# bdk2m_comm.net
KiCad netlist of a schematic drawn in Altium Designer
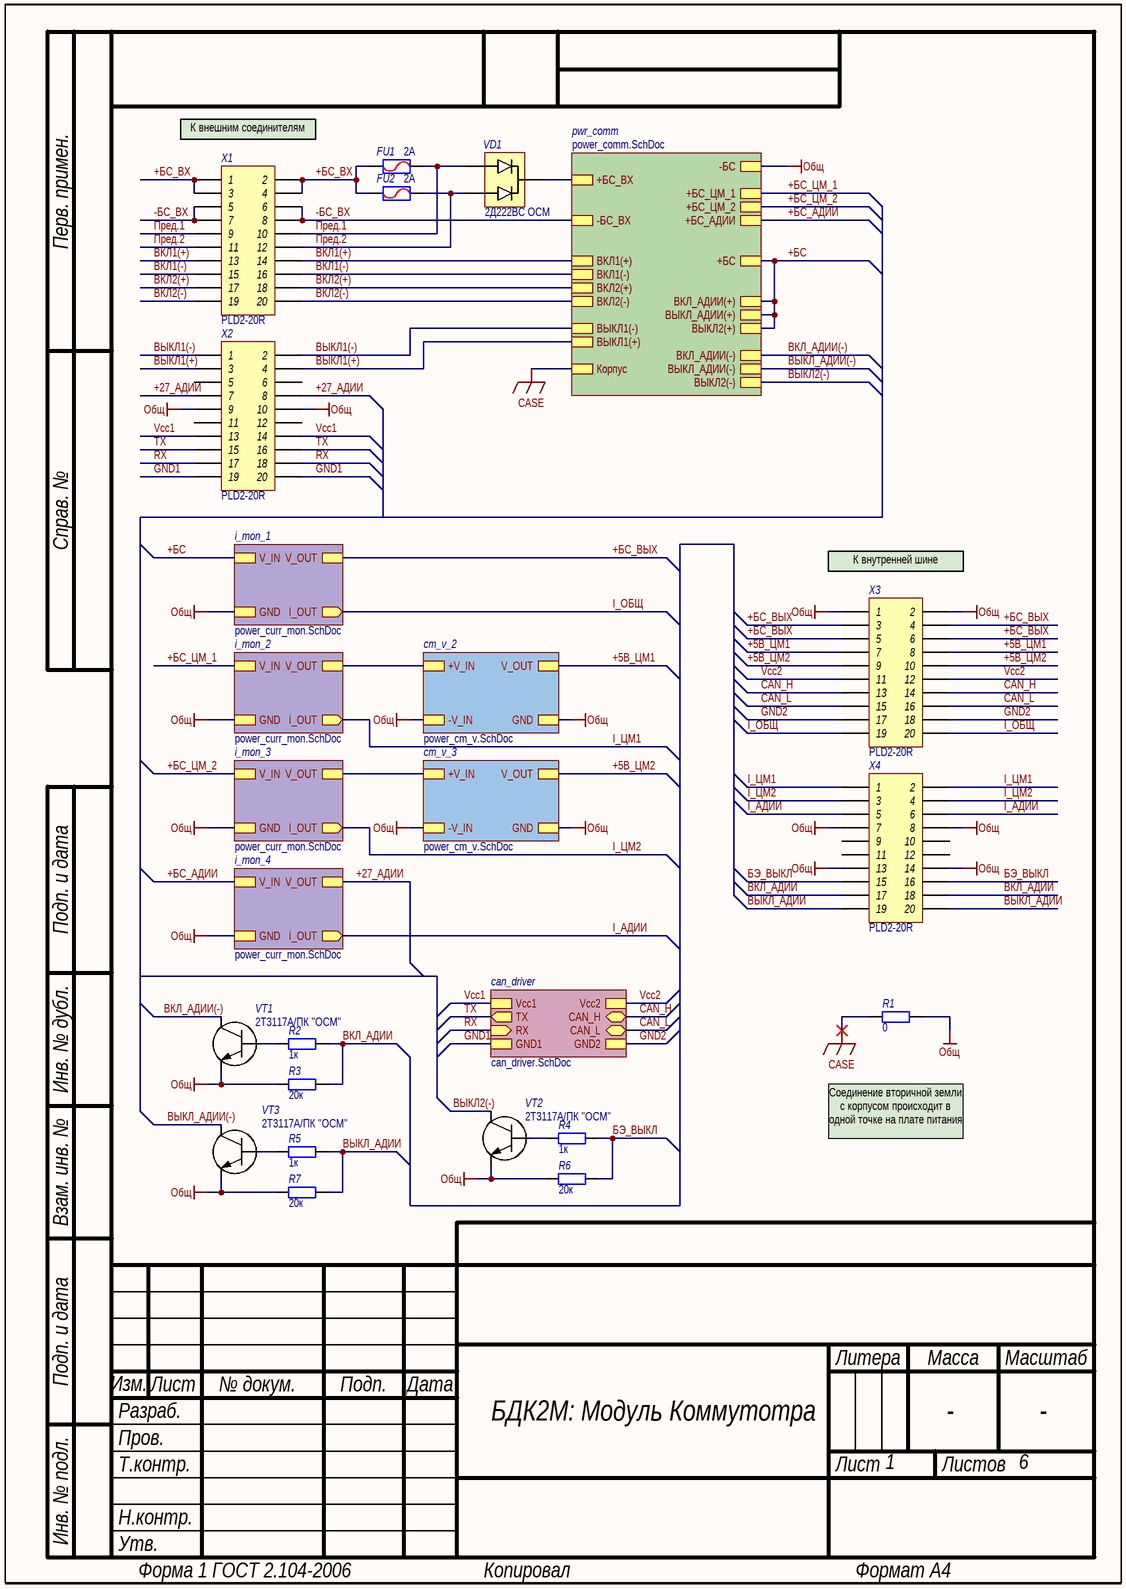
[diagram p0: bdk2m_comm.SchDoc]

(export (version "E")
  (design (tool "Eeschema 10.0.6"))
  (components
    (comp (ref "FU1")
      (value "2A")
      (footprint "VP1-2")
      (description "Предохранитель плавкий")
      (fields (field (name "Comment") "VP1-2"))
      (libsource (lib "VP1-2") (part "VP1-2"))
    )
    (comp (ref "FU2")
      (value "2A")
      (footprint "VP1-2")
      (description "Предохранитель плавкий")
      (fields (field (name "Comment") "VP1-2"))
      (libsource (lib "VP1-2") (part "VP1-2"))
    )
    (comp (ref "R1")
      (value "0")
      (footprint "SMD_0805")
      (description "Resistor")
      (libsource (lib "Passive") (part "Resistor"))
    )
    (comp (ref "R2")
      (value "1к")
      (footprint "SMD_0805")
      (description "Resistor")
      (libsource (lib "Passive") (part "Resistor"))
    )
    (comp (ref "R3")
      (value "20к")
      (footprint "SMD_0805")
      (description "Resistor")
      (libsource (lib "Passive") (part "Resistor"))
    )
    (comp (ref "R4")
      (value "1к")
      (footprint "SMD_0805")
      (description "Resistor")
      (libsource (lib "Passive") (part "Resistor"))
    )
    (comp (ref "R5")
      (value "1к")
      (footprint "SMD_0805")
      (description "Resistor")
      (libsource (lib "Passive") (part "Resistor"))
    )
    (comp (ref "R6")
      (value "20к")
      (footprint "SMD_0805")
      (description "Resistor")
      (libsource (lib "Passive") (part "Resistor"))
    )
    (comp (ref "R7")
      (value "20к")
      (footprint "SMD_0805")
      (description "Resistor")
      (libsource (lib "Passive") (part "Resistor"))
    )
    (comp (ref "VD1")
      (value "2D222VS \"OSM\"")
      (footprint "4116.4-3_offcut")
      (description "Сдвоенный диод")
      (fields (field (name "НАИМЕНОВАНИЕ") "2Д222ВС ОСМ"))
      (libsource (lib "Diod") (part "2D222"))
    )
    (comp (ref "VT1")
      (value "2T3117A")
      (footprint "TO-18")
      (description "Кремниевый биполярный\r\nэпитаксиально-планарный\r\nn-p-n транзистор")
      (fields (field (name "НАИМЕНОВАНИЕ") "2Т3117А/ПК \"ОСМ\""))
      (libsource (lib "Transistor") (part "2T3117A"))
    )
    (comp (ref "VT2")
      (value "2T3117A")
      (footprint "TO-18")
      (description "Кремниевый биполярный\r\nэпитаксиально-планарный\r\nn-p-n транзистор")
      (fields (field (name "НАИМЕНОВАНИЕ") "2Т3117А/ПК \"ОСМ\""))
      (libsource (lib "Transistor") (part "2T3117A"))
    )
    (comp (ref "VT3")
      (value "2T3117A")
      (footprint "TO-18")
      (description "Кремниевый биполярный\r\nэпитаксиально-планарный\r\nn-p-n транзистор")
      (fields (field (name "НАИМЕНОВАНИЕ") "2Т3117А/ПК \"ОСМ\""))
      (libsource (lib "Transistor") (part "2T3117A"))
    )
    (comp (ref "X1")
      (value "Header 2X10")
      (footprint "PLD2-20R")
      (description "Header, 12-Pin, Dual row")
      (fields (field (name "НАИМЕНОВАНИЕ") "PLD2-20R"))
      (libsource (lib "Connector") (part "PLD2-20"))
    )
    (comp (ref "X2")
      (value "Header 2X10")
      (footprint "PLD2-20R")
      (description "Header, 12-Pin, Dual row")
      (fields (field (name "НАИМЕНОВАНИЕ") "PLD2-20R"))
      (libsource (lib "Connector") (part "PLD2-20"))
    )
    (comp (ref "X3")
      (value "Header 2X10")
      (footprint "PLD2-20R")
      (description "Header, 12-Pin, Dual row")
      (fields (field (name "НАИМЕНОВАНИЕ") "PLD2-20R"))
      (libsource (lib "Connector") (part "PLD2-20"))
    )
    (comp (ref "X4")
      (value "Header 2X10")
      (footprint "PLD2-20R")
      (description "Header, 12-Pin, Dual row")
      (fields (field (name "НАИМЕНОВАНИЕ") "PLD2-20R"))
      (libsource (lib "Connector") (part "PLD2-20"))
    )
  )
  (nets
    (net (code "1") (name "/+5В_ЦМ1") (class "Default")
      (node (ref "X3") (pin "7") (pinfunction "7_7") (pintype "passive"))
      (node (ref "X3") (pin "8") (pinfunction "8_8") (pintype "passive"))
    )
    (net (code "2") (name "/+5В_ЦМ2") (class "Default")
      (node (ref "X3") (pin "10") (pinfunction "10_10") (pintype "passive"))
      (node (ref "X3") (pin "9") (pinfunction "9_9") (pintype "passive"))
    )
    (net (code "3") (name "/+27_АДИИ") (class "Default")
      (node (ref "X2") (pin "7") (pinfunction "7_7") (pintype "passive"))
      (node (ref "X2") (pin "8") (pinfunction "8_8") (pintype "passive"))
    )
    (net (code "8") (name "/+БС_ВХ") (class "Default")
      (node (ref "FU1") (pin "1") (pinfunction "1_1") (pintype "passive"))
      (node (ref "FU2") (pin "1") (pinfunction "1_1") (pintype "passive"))
      (node (ref "X1") (pin "1") (pinfunction "1_1") (pintype "passive"))
      (node (ref "X1") (pin "2") (pinfunction "2_2") (pintype "passive"))
      (node (ref "X1") (pin "3") (pinfunction "3_3") (pintype "passive"))
      (node (ref "X1") (pin "4") (pinfunction "4_4") (pintype "passive"))
    )
    (net (code "9") (name "/+БС_ВХ_1") (class "Default") (node (ref "VD1") (pin "8") (pintype "passive")))
    (net (code "10") (name "/+БС_ВЫХ") (class "Default")
      (node (ref "X3") (pin "3") (pinfunction "3_3") (pintype "passive"))
      (node (ref "X3") (pin "4") (pinfunction "4_4") (pintype "passive"))
      (node (ref "X3") (pin "5") (pinfunction "5_5") (pintype "passive"))
      (node (ref "X3") (pin "6") (pinfunction "6_6") (pintype "passive"))
    )
    (net (code "13") (name "/-БС_ВХ") (class "Default")
      (node (ref "X1") (pin "5") (pinfunction "5_5") (pintype "passive"))
      (node (ref "X1") (pin "6") (pinfunction "6_6") (pintype "passive"))
      (node (ref "X1") (pin "7") (pinfunction "7_7") (pintype "passive"))
      (node (ref "X1") (pin "8") (pinfunction "8_8") (pintype "passive"))
    )
    (net (code "14") (name "/CAN_H") (class "Default")
      (node (ref "X3") (pin "13") (pinfunction "13_13") (pintype "passive"))
      (node (ref "X3") (pin "14") (pinfunction "14_14") (pintype "passive"))
    )
    (net (code "15") (name "/CAN_L") (class "Default")
      (node (ref "X3") (pin "15") (pinfunction "15_15") (pintype "passive"))
      (node (ref "X3") (pin "16") (pinfunction "16_16") (pintype "passive"))
    )
    (net (code "16") (name "/GND1") (class "Default")
      (node (ref "X2") (pin "19") (pinfunction "19_19") (pintype "passive"))
      (node (ref "X2") (pin "20") (pinfunction "20_20") (pintype "passive"))
    )
    (net (code "17") (name "/GND2") (class "Default")
      (node (ref "X3") (pin "17") (pinfunction "17_17") (pintype "passive"))
      (node (ref "X3") (pin "18") (pinfunction "18_18") (pintype "passive"))
    )
    (net (code "18") (name "/I_АДИИ") (class "Default")
      (node (ref "X4") (pin "5") (pinfunction "5_5") (pintype "passive"))
      (node (ref "X4") (pin "6") (pinfunction "6_6") (pintype "passive"))
    )
    (net (code "19") (name "/I_ОБЩ") (class "Default")
      (node (ref "X3") (pin "19") (pinfunction "19_19") (pintype "passive"))
      (node (ref "X3") (pin "20") (pinfunction "20_20") (pintype "passive"))
    )
    (net (code "20") (name "/I_ЦМ1") (class "Default")
      (node (ref "X4") (pin "1") (pinfunction "1_1") (pintype "passive"))
      (node (ref "X4") (pin "2") (pinfunction "2_2") (pintype "passive"))
    )
    (net (code "21") (name "/I_ЦМ2") (class "Default")
      (node (ref "X4") (pin "3") (pinfunction "3_3") (pintype "passive"))
      (node (ref "X4") (pin "4") (pinfunction "4_4") (pintype "passive"))
    )
    (net (code "22") (name "/RX") (class "Default")
      (node (ref "X2") (pin "17") (pinfunction "17_17") (pintype "passive"))
      (node (ref "X2") (pin "18") (pinfunction "18_18") (pintype "passive"))
    )
    (net (code "23") (name "/TX") (class "Default")
      (node (ref "X2") (pin "15") (pinfunction "15_15") (pintype "passive"))
      (node (ref "X2") (pin "16") (pinfunction "16_16") (pintype "passive"))
    )
    (net (code "24") (name "/Vcc1") (class "Default")
      (node (ref "X2") (pin "13") (pinfunction "13_13") (pintype "passive"))
      (node (ref "X2") (pin "14") (pinfunction "14_14") (pintype "passive"))
    )
    (net (code "25") (name "/Vcc2") (class "Default")
      (node (ref "X3") (pin "11") (pinfunction "11_11") (pintype "passive"))
      (node (ref "X3") (pin "12") (pinfunction "12_12") (pintype "passive"))
    )
    (net (code "26") (name "/БЭ_ВЫКЛ") (class "Default")
      (node (ref "R4") (pin "2") (pinfunction "2_2") (pintype "passive"))
      (node (ref "R6") (pin "2") (pinfunction "2_2") (pintype "passive"))
      (node (ref "X4") (pin "15") (pinfunction "15_15") (pintype "passive"))
      (node (ref "X4") (pin "16") (pinfunction "16_16") (pintype "passive"))
    )
    (net (code "27") (name "/ВКЛ1(+)") (class "Default")
      (node (ref "X1") (pin "13") (pinfunction "13_13") (pintype "passive"))
      (node (ref "X1") (pin "14") (pinfunction "14_14") (pintype "passive"))
    )
    (net (code "28") (name "/ВКЛ1(-)") (class "Default")
      (node (ref "X1") (pin "15") (pinfunction "15_15") (pintype "passive"))
      (node (ref "X1") (pin "16") (pinfunction "16_16") (pintype "passive"))
    )
    (net (code "29") (name "/ВКЛ2(+)") (class "Default")
      (node (ref "X1") (pin "17") (pinfunction "17_17") (pintype "passive"))
      (node (ref "X1") (pin "18") (pinfunction "18_18") (pintype "passive"))
    )
    (net (code "30") (name "/ВКЛ2(-)") (class "Default")
      (node (ref "X1") (pin "19") (pinfunction "19_19") (pintype "passive"))
      (node (ref "X1") (pin "20") (pinfunction "20_20") (pintype "passive"))
    )
    (net (code "31") (name "/ВКЛ_АДИИ") (class "Default")
      (node (ref "R2") (pin "2") (pinfunction "2_2") (pintype "passive"))
      (node (ref "R3") (pin "2") (pinfunction "2_2") (pintype "passive"))
      (node (ref "X4") (pin "17") (pinfunction "17_17") (pintype "passive"))
      (node (ref "X4") (pin "18") (pinfunction "18_18") (pintype "passive"))
    )
    (net (code "32") (name "/ВКЛ_АДИИ(-)") (class "Default")
      (node (ref "VT1") (pin "3") (pinfunction "COLLECTOR_3") (pintype "passive"))
    )
    (net (code "33") (name "/ВЫКЛ1(+)") (class "Default")
      (node (ref "X2") (pin "3") (pinfunction "3_3") (pintype "passive"))
      (node (ref "X2") (pin "4") (pinfunction "4_4") (pintype "passive"))
    )
    (net (code "34") (name "/ВЫКЛ1(-)") (class "Default")
      (node (ref "X2") (pin "1") (pinfunction "1_1") (pintype "passive"))
      (node (ref "X2") (pin "2") (pinfunction "2_2") (pintype "passive"))
    )
    (net (code "35") (name "/ВЫКЛ2(-)") (class "Default")
      (node (ref "VT2") (pin "3") (pinfunction "COLLECTOR_3") (pintype "passive"))
    )
    (net (code "36") (name "/ВЫКЛ_АДИИ") (class "Default")
      (node (ref "R5") (pin "2") (pinfunction "2_2") (pintype "passive"))
      (node (ref "R7") (pin "2") (pinfunction "2_2") (pintype "passive"))
      (node (ref "X4") (pin "19") (pinfunction "19_19") (pintype "passive"))
      (node (ref "X4") (pin "20") (pinfunction "20_20") (pintype "passive"))
    )
    (net (code "37") (name "/ВЫКЛ_АДИИ(-)") (class "Default")
      (node (ref "VT3") (pin "3") (pinfunction "COLLECTOR_3") (pintype "passive"))
    )
    (net (code "38") (name "/Пред.1") (class "Default")
      (node (ref "FU1") (pin "2") (pinfunction "2_2") (pintype "passive"))
      (node (ref "VD1") (pin "11") (pintype "passive"))
      (node (ref "X1") (pin "10") (pinfunction "10_10") (pintype "passive"))
      (node (ref "X1") (pin "9") (pinfunction "9_9") (pintype "passive"))
    )
    (net (code "39") (name "/Пред.2") (class "Default")
      (node (ref "FU2") (pin "2") (pinfunction "2_2") (pintype "passive"))
      (node (ref "VD1") (pin "17") (pintype "passive"))
      (node (ref "X1") (pin "11") (pinfunction "11_11") (pintype "passive"))
      (node (ref "X1") (pin "12") (pinfunction "12_12") (pintype "passive"))
    )
    (net (code "40") (name "CASE") (class "Default")
      (node (ref "R1") (pin "1") (pinfunction "1_1") (pintype "passive"))
    )
    (net (code "41") (name "Net-(VT1-BASE)") (class "Default")
      (node (ref "R2") (pin "1") (pinfunction "1_1") (pintype "passive"))
      (node (ref "VT1") (pin "2") (pinfunction "BASE_2") (pintype "passive"))
    )
    (net (code "42") (name "Net-(VT2-BASE)") (class "Default")
      (node (ref "R4") (pin "1") (pinfunction "1_1") (pintype "passive"))
      (node (ref "VT2") (pin "2") (pinfunction "BASE_2") (pintype "passive"))
    )
    (net (code "43") (name "Net-(VT3-BASE)") (class "Default")
      (node (ref "R5") (pin "1") (pinfunction "1_1") (pintype "passive"))
      (node (ref "VT3") (pin "2") (pinfunction "BASE_2") (pintype "passive"))
    )
    (net (code "44") (name "unconnected-(X2-Pad5)") (class "Default")
      (node (ref "X2") (pin "5") (pinfunction "5_5") (pintype "passive"))
    )
    (net (code "45") (name "unconnected-(X2-Pad6)") (class "Default")
      (node (ref "X2") (pin "6") (pinfunction "6_6") (pintype "passive"))
    )
    (net (code "46") (name "unconnected-(X2-Pad11)") (class "Default")
      (node (ref "X2") (pin "11") (pinfunction "11_11") (pintype "passive"))
    )
    (net (code "47") (name "unconnected-(X2-Pad12)") (class "Default")
      (node (ref "X2") (pin "12") (pinfunction "12_12") (pintype "passive"))
    )
    (net (code "48") (name "unconnected-(X4-Pad9)") (class "Default")
      (node (ref "X4") (pin "9") (pinfunction "9_9") (pintype "passive"))
    )
    (net (code "49") (name "unconnected-(X4-Pad10)") (class "Default")
      (node (ref "X4") (pin "10") (pinfunction "10_10") (pintype "passive"))
    )
    (net (code "50") (name "unconnected-(X4-Pad11)") (class "Default")
      (node (ref "X4") (pin "11") (pinfunction "11_11") (pintype "passive"))
    )
    (net (code "51") (name "unconnected-(X4-Pad12)") (class "Default")
      (node (ref "X4") (pin "12") (pinfunction "12_12") (pintype "passive"))
    )
    (net (code "52") (name "Общ") (class "Default")
      (node (ref "R1") (pin "2") (pinfunction "2_2") (pintype "passive"))
      (node (ref "R3") (pin "1") (pinfunction "1_1") (pintype "passive"))
      (node (ref "R6") (pin "1") (pinfunction "1_1") (pintype "passive"))
      (node (ref "R7") (pin "1") (pinfunction "1_1") (pintype "passive"))
      (node (ref "VT1") (pin "1") (pinfunction "EMITTER_1") (pintype "passive"))
      (node (ref "VT2") (pin "1") (pinfunction "EMITTER_1") (pintype "passive"))
      (node (ref "VT3") (pin "1") (pinfunction "EMITTER_1") (pintype "passive"))
      (node (ref "X2") (pin "10") (pinfunction "10_10") (pintype "passive"))
      (node (ref "X2") (pin "9") (pinfunction "9_9") (pintype "passive"))
      (node (ref "X3") (pin "1") (pinfunction "1_1") (pintype "passive"))
      (node (ref "X3") (pin "2") (pinfunction "2_2") (pintype "passive"))
      (node (ref "X4") (pin "13") (pinfunction "13_13") (pintype "passive"))
      (node (ref "X4") (pin "14") (pinfunction "14_14") (pintype "passive"))
      (node (ref "X4") (pin "7") (pinfunction "7_7") (pintype "passive"))
      (node (ref "X4") (pin "8") (pinfunction "8_8") (pintype "passive"))
    )
  )
)
